# ProcessorSupport.net
KiCad netlist of a schematic drawn in Altium Designer
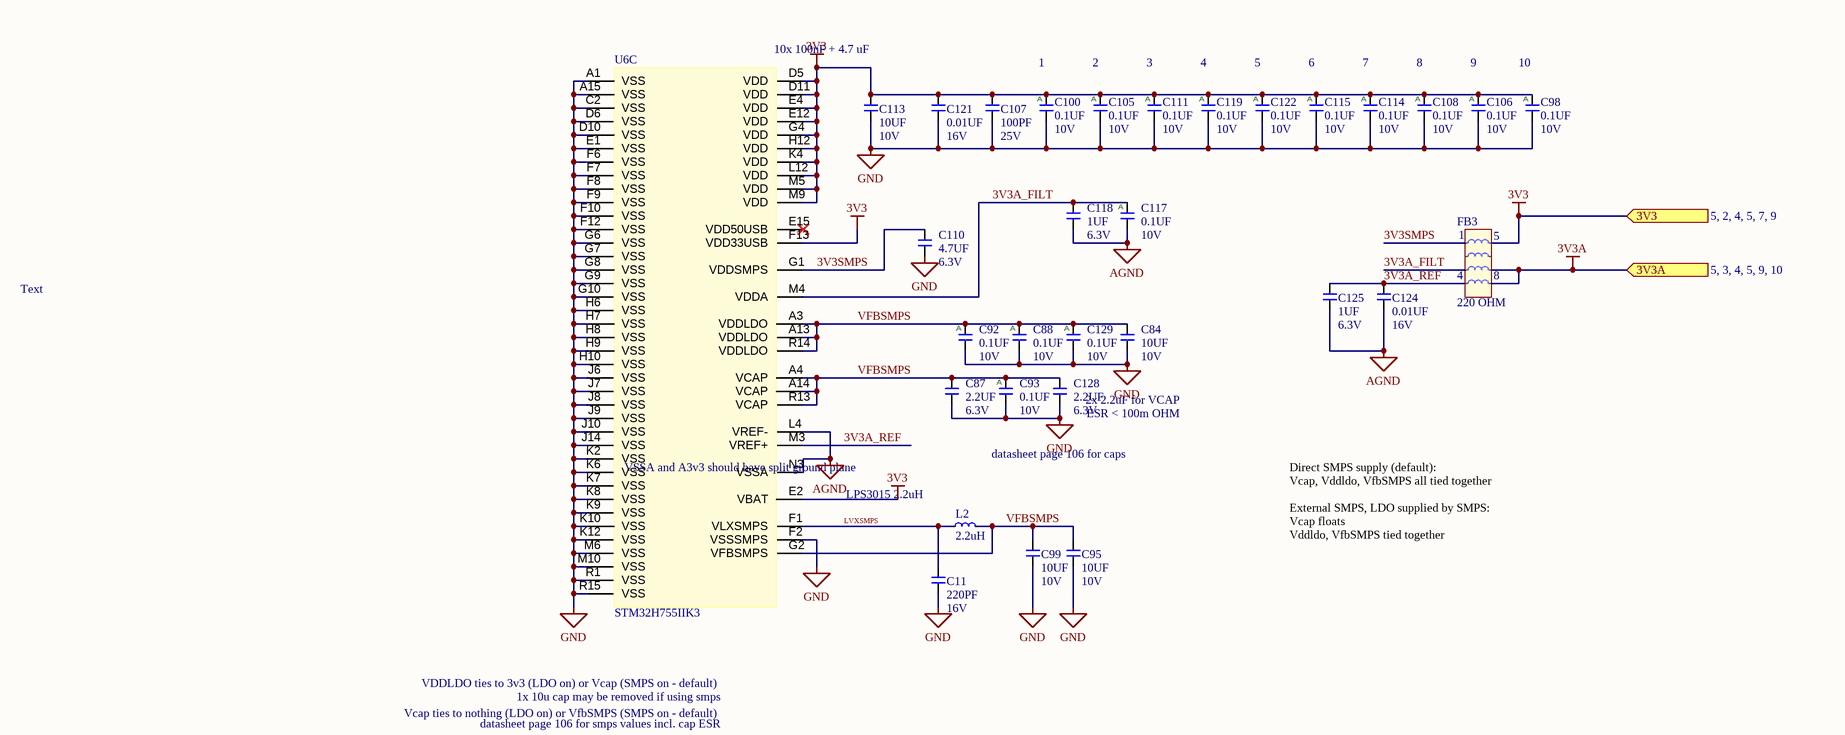
[diagram p0: ProcessorSupport.SchDoc]

(export (version "E")
  (design (tool "Eeschema 10.0.6"))
  (components
    (comp (ref "C11")
      (value "220PF")
      (footprint "C0201")
      (description "CAP, CER, X7R, 220pF, 16V, 10%, 0201, 0.33mm T")
      (fields
        (field (name "MFG") "MURATA")
        (field (name "VOLTAGE") "16V")
        (field (name "Comment") "__Template_Cap")
      )
      (libsource (lib "AltiumReleaseLibDB") (part "__Template_Cap"))
    )
    (comp (ref "C84")
      (value "10UF")
      (footprint "C0402")
      (description "CAP, CER, X5R, 10uF, 10V, 20%, 0402, 0.7mm T")
      (fields
        (field (name "MFG") "SAMSUNG")
        (field (name "VOLTAGE") "10V")
        (field (name "Comment") "__Template_Cap")
      )
      (libsource (lib "AltiumReleaseLibDB") (part "__Template_Cap"))
    )
    (comp (ref "C87")
      (value "2.2UF")
      (footprint "C0201")
      (description "CAP, CER, X5R, 2.2uF, 6.3V, 20%, 0201, 0.39mm T")
      (fields
        (field (name "MFG") "SAMSUNG")
        (field (name "VOLTAGE") "6.3V")
        (field (name "Comment") "__Template_Cap")
      )
      (libsource (lib "AltiumReleaseLibDB") (part "__Template_Cap"))
    )
    (comp (ref "C88")
      (value "0.1UF")
      (footprint "C0201")
      (description "CAP, CER, X6S, 0.1uF, 10V, 10%, 0201, AUTOGRADE")
      (fields
        (field (name "MFG") "MURATA")
        (field (name "VOLTAGE") "10V")
        (field (name "Comment") "__Template_Cap_Auto")
      )
      (libsource (lib "AltiumReleaseLibDB") (part "__Template_Cap_Auto"))
    )
    (comp (ref "C92")
      (value "0.1UF")
      (footprint "C0201")
      (description "CAP, CER, X6S, 0.1uF, 10V, 10%, 0201, AUTOGRADE")
      (fields
        (field (name "MFG") "MURATA")
        (field (name "VOLTAGE") "10V")
        (field (name "Comment") "__Template_Cap_Auto")
      )
      (libsource (lib "AltiumReleaseLibDB") (part "__Template_Cap_Auto"))
    )
    (comp (ref "C93")
      (value "0.1UF")
      (footprint "C0201")
      (description "CAP, CER, X6S, 0.1uF, 10V, 10%, 0201, AUTOGRADE")
      (fields
        (field (name "MFG") "MURATA")
        (field (name "VOLTAGE") "10V")
        (field (name "Comment") "__Template_Cap_Auto")
      )
      (libsource (lib "AltiumReleaseLibDB") (part "__Template_Cap_Auto"))
    )
    (comp (ref "C95")
      (value "10UF")
      (footprint "C0402")
      (description "CAP, CER, X5R, 10uF, 10V, 20%, 0402, 0.7mm T")
      (fields
        (field (name "MFG") "SAMSUNG")
        (field (name "VOLTAGE") "10V")
        (field (name "Comment") "__Template_Cap")
      )
      (libsource (lib "AltiumReleaseLibDB") (part "__Template_Cap"))
    )
    (comp (ref "C98")
      (value "0.1UF")
      (footprint "C0201")
      (description "CAP, CER, X6S, 0.1uF, 10V, 10%, 0201, AUTOGRADE")
      (fields
        (field (name "MFG") "MURATA")
        (field (name "VOLTAGE") "10V")
        (field (name "Comment") "__Template_Cap_Auto")
      )
      (libsource (lib "AltiumReleaseLibDB") (part "__Template_Cap_Auto"))
    )
    (comp (ref "C99")
      (value "10UF")
      (footprint "C0402")
      (description "CAP, CER, X5R, 10uF, 10V, 20%, 0402, 0.7mm T")
      (fields
        (field (name "MFG") "SAMSUNG")
        (field (name "VOLTAGE") "10V")
        (field (name "Comment") "__Template_Cap")
      )
      (libsource (lib "AltiumReleaseLibDB") (part "__Template_Cap"))
    )
    (comp (ref "C100")
      (value "0.1UF")
      (footprint "C0201")
      (description "CAP, CER, X6S, 0.1uF, 10V, 10%, 0201, AUTOGRADE")
      (fields
        (field (name "MFG") "MURATA")
        (field (name "VOLTAGE") "10V")
        (field (name "Comment") "__Template_Cap_Auto")
      )
      (libsource (lib "AltiumReleaseLibDB") (part "__Template_Cap_Auto"))
    )
    (comp (ref "C105")
      (value "0.1UF")
      (footprint "C0201")
      (description "CAP, CER, X6S, 0.1uF, 10V, 10%, 0201, AUTOGRADE")
      (fields
        (field (name "MFG") "MURATA")
        (field (name "VOLTAGE") "10V")
        (field (name "Comment") "__Template_Cap_Auto")
      )
      (libsource (lib "AltiumReleaseLibDB") (part "__Template_Cap_Auto"))
    )
    (comp (ref "C106")
      (value "0.1UF")
      (footprint "C0201")
      (description "CAP, CER, X6S, 0.1uF, 10V, 10%, 0201, AUTOGRADE")
      (fields
        (field (name "MFG") "MURATA")
        (field (name "VOLTAGE") "10V")
        (field (name "Comment") "__Template_Cap_Auto")
      )
      (libsource (lib "AltiumReleaseLibDB") (part "__Template_Cap_Auto"))
    )
    (comp (ref "C107")
      (value "100PF")
      (footprint "C0201")
      (description "CAP, CER, X7R, 100pF, 25V, 10%, 0201, 0.33mm T")
      (fields
        (field (name "MFG") "MURATA")
        (field (name "VOLTAGE") "25V")
        (field (name "Comment") "__Template_Cap")
      )
      (libsource (lib "AltiumReleaseLibDB") (part "__Template_Cap"))
    )
    (comp (ref "C108")
      (value "0.1UF")
      (footprint "C0201")
      (description "CAP, CER, X6S, 0.1uF, 10V, 10%, 0201, AUTOGRADE")
      (fields
        (field (name "MFG") "MURATA")
        (field (name "VOLTAGE") "10V")
        (field (name "Comment") "__Template_Cap_Auto")
      )
      (libsource (lib "AltiumReleaseLibDB") (part "__Template_Cap_Auto"))
    )
    (comp (ref "C110")
      (value "4.7UF")
      (footprint "C0402")
      (description "CAP, CER, X5R, 4.7uF, 20%, 6.3V, 0402, 0.65mm")
      (fields
        (field (name "MFG") "TDK")
        (field (name "VOLTAGE") "6.3V")
        (field (name "Comment") "__Template_Cap")
      )
      (libsource (lib "AltiumReleaseLibDB") (part "__Template_Cap"))
    )
    (comp (ref "C111")
      (value "0.1UF")
      (footprint "C0201")
      (description "CAP, CER, X6S, 0.1uF, 10V, 10%, 0201, AUTOGRADE")
      (fields
        (field (name "MFG") "MURATA")
        (field (name "VOLTAGE") "10V")
        (field (name "Comment") "__Template_Cap_Auto")
      )
      (libsource (lib "AltiumReleaseLibDB") (part "__Template_Cap_Auto"))
    )
    (comp (ref "C113")
      (value "10UF")
      (footprint "C0402")
      (description "CAP, CER, X5R, 10uF, 10V, 20%, 0402, 0.7mm T")
      (fields
        (field (name "MFG") "SAMSUNG")
        (field (name "VOLTAGE") "10V")
        (field (name "Comment") "__Template_Cap")
      )
      (libsource (lib "AltiumReleaseLibDB") (part "__Template_Cap"))
    )
    (comp (ref "C114")
      (value "0.1UF")
      (footprint "C0201")
      (description "CAP, CER, X6S, 0.1uF, 10V, 10%, 0201, AUTOGRADE")
      (fields
        (field (name "MFG") "MURATA")
        (field (name "VOLTAGE") "10V")
        (field (name "Comment") "__Template_Cap_Auto")
      )
      (libsource (lib "AltiumReleaseLibDB") (part "__Template_Cap_Auto"))
    )
    (comp (ref "C115")
      (value "0.1UF")
      (footprint "C0201")
      (description "CAP, CER, X6S, 0.1uF, 10V, 10%, 0201, AUTOGRADE")
      (fields
        (field (name "MFG") "MURATA")
        (field (name "VOLTAGE") "10V")
        (field (name "Comment") "__Template_Cap_Auto")
      )
      (libsource (lib "AltiumReleaseLibDB") (part "__Template_Cap_Auto"))
    )
    (comp (ref "C117")
      (value "0.1UF")
      (footprint "C0201")
      (description "CAP, CER, X6S, 0.1uF, 10V, 10%, 0201, AUTOGRADE")
      (fields
        (field (name "MFG") "MURATA")
        (field (name "VOLTAGE") "10V")
        (field (name "Comment") "__Template_Cap_Auto")
      )
      (libsource (lib "AltiumReleaseLibDB") (part "__Template_Cap_Auto"))
    )
    (comp (ref "C118")
      (value "1UF")
      (footprint "C0201")
      (description "CAP, CER, X5R, 1uF, 6.3V, 20%, 0201, 0.33mm T")
      (fields
        (field (name "MFG") "SAMSUNG")
        (field (name "VOLTAGE") "6.3V")
        (field (name "Comment") "__Template_Cap")
      )
      (libsource (lib "AltiumReleaseLibDB") (part "__Template_Cap"))
    )
    (comp (ref "C119")
      (value "0.1UF")
      (footprint "C0201")
      (description "CAP, CER, X6S, 0.1uF, 10V, 10%, 0201, AUTOGRADE")
      (fields
        (field (name "MFG") "MURATA")
        (field (name "VOLTAGE") "10V")
        (field (name "Comment") "__Template_Cap_Auto")
      )
      (libsource (lib "AltiumReleaseLibDB") (part "__Template_Cap_Auto"))
    )
    (comp (ref "C121")
      (value "0.01UF")
      (footprint "C0201")
      (description "CAP, CER, X5R, 0.01uF, 16V, 10%, 0201, 0.33mm T")
      (fields
        (field (name "MFG") "MURATA")
        (field (name "VOLTAGE") "16V")
        (field (name "Comment") "__Template_Cap")
      )
      (libsource (lib "AltiumReleaseLibDB") (part "__Template_Cap"))
    )
    (comp (ref "C122")
      (value "0.1UF")
      (footprint "C0201")
      (description "CAP, CER, X6S, 0.1uF, 10V, 10%, 0201, AUTOGRADE")
      (fields
        (field (name "MFG") "MURATA")
        (field (name "VOLTAGE") "10V")
        (field (name "Comment") "__Template_Cap_Auto")
      )
      (libsource (lib "AltiumReleaseLibDB") (part "__Template_Cap_Auto"))
    )
    (comp (ref "C124")
      (value "0.01UF")
      (footprint "C0201")
      (description "CAP, CER, X5R, 0.01uF, 16V, 10%, 0201, 0.33mm T")
      (fields
        (field (name "MFG") "MURATA")
        (field (name "VOLTAGE") "16V")
        (field (name "Comment") "__Template_Cap")
      )
      (libsource (lib "AltiumReleaseLibDB") (part "__Template_Cap"))
    )
    (comp (ref "C125")
      (value "1UF")
      (footprint "C0201")
      (description "CAP, CER, X5R, 1uF, 6.3V, 20%, 0201, 0.33mm T")
      (fields
        (field (name "MFG") "SAMSUNG")
        (field (name "VOLTAGE") "6.3V")
        (field (name "Comment") "__Template_Cap")
      )
      (libsource (lib "AltiumReleaseLibDB") (part "__Template_Cap"))
    )
    (comp (ref "C128")
      (value "2.2UF")
      (footprint "C0201")
      (description "CAP, CER, X5R, 2.2uF, 6.3V, 20%, 0201, 0.39mm T")
      (fields
        (field (name "MFG") "SAMSUNG")
        (field (name "VOLTAGE") "6.3V")
        (field (name "Comment") "__Template_Cap")
      )
      (libsource (lib "AltiumReleaseLibDB") (part "__Template_Cap"))
    )
    (comp (ref "C129")
      (value "0.1UF")
      (footprint "C0201")
      (description "CAP, CER, X6S, 0.1uF, 10V, 10%, 0201, AUTOGRADE")
      (fields
        (field (name "MFG") "MURATA")
        (field (name "VOLTAGE") "10V")
        (field (name "Comment") "__Template_Cap_Auto")
      )
      (libsource (lib "AltiumReleaseLibDB") (part "__Template_Cap_Auto"))
    )
    (comp (ref "FB3")
      (value "220 OHM")
      (footprint "FB_ARRAY_BLA31AG221SN4D")
      (description "FERRITE, BEAD, 220 OHM, 150mA, DCR 0.25 MAX, 1206")
      (fields (field (name "MFG") "Murata Electronics") (field (name "Comment") "FB_ARRAY_BLA31AG221SN4D"))
      (libsource (lib "AltiumReleaseLibDB") (part "FB_ARRAY_BLA31AG221SN4D"))
    )
    (comp (ref "L2")
      (value "2.2uH")
      (footprint "IND_LPS3015-152MRB")
      (description "IND, WIREWOUND, SHIELDED, 2.2uH, 2.1A, 20%, DCR 0.11, SMD, AUTOGRADE")
      (fields (field (name "MFG") "COILCRAFT") (field (name "Comment") "__Template_Inductor"))
      (libsource (lib "AltiumReleaseLibDB") (part "__Template_Inductor"))
    )
    (comp (ref "U6")
      (value "MCU_STM32H755IIK3")
      (footprint "BGS201C65P15X15_1000X1000X60")
      (description "IC, MCU, STM32H755xI, ARM, 32-BIT, 240MHZ, 128 I/O, 2MB, FLASH, 1.62V TO 3.6V, UFBGA-201")
      (fields (field (name "MFG") "STMicroelectronics") (field (name "MFG P/N") "STM32H755IIK3"))
      (libsource (lib "AltiumReleaseLibDB") (part "MCU_STM32H755IIK3"))
    )
  )
  (nets
    (net (code "1") (name "/3V3A_FILT") (class "Default")
      (node (ref "C117") (pin "1") (pintype "passive"))
      (node (ref "C118") (pin "1") (pintype "passive"))
      (node (ref "FB3") (pin "3") (pinfunction "3_3") (pintype "passive"))
      (node (ref "U6") (pin "M4") (pinfunction "VDDA_M4") (pintype "power_in"))
    )
    (net (code "2") (name "/3V3A_REF") (class "Default")
      (node (ref "C124") (pin "1") (pintype "passive"))
      (node (ref "C125") (pin "1") (pintype "passive"))
      (node (ref "FB3") (pin "4") (pinfunction "4_4") (pintype "passive"))
      (node (ref "U6") (pin "M3") (pinfunction "VREF+_M3") (pintype "power_in"))
    )
    (net (code "3") (name "/3V3SMPS") (class "Default")
      (node (ref "C110") (pin "1") (pintype "passive"))
      (node (ref "FB3") (pin "1") (pinfunction "1_1") (pintype "passive"))
      (node (ref "U6") (pin "G1") (pinfunction "VDDSMPS_G1") (pintype "power_in"))
    )
    (net (code "4") (name "/LVXSMPS") (class "Default")
      (node (ref "C11") (pin "1") (pintype "passive"))
      (node (ref "L2") (pin "1") (pintype "passive"))
      (node (ref "U6") (pin "F1") (pinfunction "VLXSMPS_F1") (pintype "power_in"))
    )
    (net (code "5") (name "/VFBSMPS") (class "Default")
      (node (ref "C128") (pin "1") (pintype "passive"))
      (node (ref "C129") (pin "1") (pintype "passive"))
      (node (ref "C84") (pin "1") (pintype "passive"))
      (node (ref "C87") (pin "1") (pintype "passive"))
      (node (ref "C88") (pin "1") (pintype "passive"))
      (node (ref "C92") (pin "1") (pintype "passive"))
      (node (ref "C93") (pin "1") (pintype "passive"))
      (node (ref "C95") (pin "2") (pintype "passive"))
      (node (ref "C99") (pin "2") (pintype "passive"))
      (node (ref "L2") (pin "2") (pintype "passive"))
      (node (ref "U6") (pin "A13") (pinfunction "VDDLDO_A13") (pintype "power_in"))
      (node (ref "U6") (pin "A14") (pinfunction "VCAP_A14") (pintype "power_in"))
      (node (ref "U6") (pin "A3") (pinfunction "VDDLDO_A3") (pintype "power_in"))
      (node (ref "U6") (pin "A4") (pinfunction "VCAP_A4") (pintype "power_in"))
      (node (ref "U6") (pin "G2") (pinfunction "VFBSMPS_G2") (pintype "power_in"))
      (node (ref "U6") (pin "R13") (pinfunction "VCAP_R13") (pintype "power_in"))
      (node (ref "U6") (pin "R14") (pinfunction "VDDLDO_R14") (pintype "power_in"))
    )
    (net (code "6") (name "3V3") (class "Default")
      (node (ref "C100") (pin "1") (pintype "passive"))
      (node (ref "C105") (pin "1") (pintype "passive"))
      (node (ref "C106") (pin "1") (pintype "passive"))
      (node (ref "C107") (pin "1") (pintype "passive"))
      (node (ref "C108") (pin "1") (pintype "passive"))
      (node (ref "C111") (pin "1") (pintype "passive"))
      (node (ref "C113") (pin "1") (pintype "passive"))
      (node (ref "C114") (pin "1") (pintype "passive"))
      (node (ref "C115") (pin "1") (pintype "passive"))
      (node (ref "C119") (pin "1") (pintype "passive"))
      (node (ref "C121") (pin "1") (pintype "passive"))
      (node (ref "C122") (pin "1") (pintype "passive"))
      (node (ref "C98") (pin "1") (pintype "passive"))
      (node (ref "FB3") (pin "5") (pinfunction "5_5") (pintype "passive"))
      (node (ref "U6") (pin "D11") (pinfunction "VDD_D11") (pintype "power_in"))
      (node (ref "U6") (pin "D5") (pinfunction "VDD_D5") (pintype "power_in"))
      (node (ref "U6") (pin "E12") (pinfunction "VDD_E12") (pintype "power_in"))
      (node (ref "U6") (pin "E2") (pinfunction "VBAT_E2") (pintype "power_in"))
      (node (ref "U6") (pin "E4") (pinfunction "VDD_E4") (pintype "power_in"))
      (node (ref "U6") (pin "F13") (pinfunction "VDD33USB_F13") (pintype "power_in"))
      (node (ref "U6") (pin "G4") (pinfunction "VDD_G4") (pintype "power_in"))
      (node (ref "U6") (pin "H12") (pinfunction "VDD_H12") (pintype "power_in"))
      (node (ref "U6") (pin "K4") (pinfunction "VDD_K4") (pintype "power_in"))
      (node (ref "U6") (pin "L12") (pinfunction "VDD_L12") (pintype "power_in"))
      (node (ref "U6") (pin "M5") (pinfunction "VDD_M5") (pintype "power_in"))
      (node (ref "U6") (pin "M9") (pinfunction "VDD_M9") (pintype "power_in"))
    )
    (net (code "7") (name "3V3A") (class "Default")
      (node (ref "FB3") (pin "7") (pinfunction "7_7") (pintype "passive"))
      (node (ref "FB3") (pin "8") (pinfunction "8_8") (pintype "passive"))
    )
    (net (code "8") (name "AGND") (class "Default")
      (node (ref "C117") (pin "2") (pintype "passive"))
      (node (ref "C118") (pin "2") (pintype "passive"))
      (node (ref "C124") (pin "2") (pintype "passive"))
      (node (ref "C125") (pin "2") (pintype "passive"))
      (node (ref "U6") (pin "L4") (pinfunction "VREF-_L4") (pintype "power_in"))
      (node (ref "U6") (pin "N3") (pinfunction "VSSA_N3") (pintype "power_in"))
    )
    (net (code "9") (name "GND") (class "Default")
      (node (ref "C100") (pin "2") (pintype "passive"))
      (node (ref "C105") (pin "2") (pintype "passive"))
      (node (ref "C106") (pin "2") (pintype "passive"))
      (node (ref "C107") (pin "2") (pintype "passive"))
      (node (ref "C108") (pin "2") (pintype "passive"))
      (node (ref "C11") (pin "2") (pintype "passive"))
      (node (ref "C110") (pin "2") (pintype "passive"))
      (node (ref "C111") (pin "2") (pintype "passive"))
      (node (ref "C113") (pin "2") (pintype "passive"))
      (node (ref "C114") (pin "2") (pintype "passive"))
      (node (ref "C115") (pin "2") (pintype "passive"))
      (node (ref "C119") (pin "2") (pintype "passive"))
      (node (ref "C121") (pin "2") (pintype "passive"))
      (node (ref "C122") (pin "2") (pintype "passive"))
      (node (ref "C128") (pin "2") (pintype "passive"))
      (node (ref "C129") (pin "2") (pintype "passive"))
      (node (ref "C84") (pin "2") (pintype "passive"))
      (node (ref "C87") (pin "2") (pintype "passive"))
      (node (ref "C88") (pin "2") (pintype "passive"))
      (node (ref "C92") (pin "2") (pintype "passive"))
      (node (ref "C93") (pin "2") (pintype "passive"))
      (node (ref "C95") (pin "1") (pintype "passive"))
      (node (ref "C98") (pin "2") (pintype "passive"))
      (node (ref "C99") (pin "1") (pintype "passive"))
      (node (ref "U6") (pin "A1") (pinfunction "VSS_A1") (pintype "power_in"))
      (node (ref "U6") (pin "A15") (pinfunction "VSS_A15") (pintype "power_in"))
      (node (ref "U6") (pin "C2") (pinfunction "VSS_C2") (pintype "power_in"))
      (node (ref "U6") (pin "D10") (pinfunction "VSS_D10") (pintype "power_in"))
      (node (ref "U6") (pin "D6") (pinfunction "VSS_D6") (pintype "power_in"))
      (node (ref "U6") (pin "E1") (pinfunction "VSS_E1") (pintype "power_in"))
      (node (ref "U6") (pin "F10") (pinfunction "VSS_F10") (pintype "power_in"))
      (node (ref "U6") (pin "F12") (pinfunction "VSS_F12") (pintype "power_in"))
      (node (ref "U6") (pin "F2") (pinfunction "VSSSMPS_F2") (pintype "power_in"))
      (node (ref "U6") (pin "F6") (pinfunction "VSS_F6") (pintype "power_in"))
      (node (ref "U6") (pin "F7") (pinfunction "VSS_F7") (pintype "power_in"))
      (node (ref "U6") (pin "F8") (pinfunction "VSS_F8") (pintype "power_in"))
      (node (ref "U6") (pin "F9") (pinfunction "VSS_F9") (pintype "power_in"))
      (node (ref "U6") (pin "G10") (pinfunction "VSS_G10") (pintype "power_in"))
      (node (ref "U6") (pin "G6") (pinfunction "VSS_G6") (pintype "power_in"))
      (node (ref "U6") (pin "G7") (pinfunction "VSS_G7") (pintype "power_in"))
      (node (ref "U6") (pin "G8") (pinfunction "VSS_G8") (pintype "power_in"))
      (node (ref "U6") (pin "G9") (pinfunction "VSS_G9") (pintype "power_in"))
      (node (ref "U6") (pin "H10") (pinfunction "VSS_H10") (pintype "power_in"))
      (node (ref "U6") (pin "H6") (pinfunction "VSS_H6") (pintype "power_in"))
      (node (ref "U6") (pin "H7") (pinfunction "VSS_H7") (pintype "power_in"))
      (node (ref "U6") (pin "H8") (pinfunction "VSS_H8") (pintype "power_in"))
      (node (ref "U6") (pin "H9") (pinfunction "VSS_H9") (pintype "power_in"))
      (node (ref "U6") (pin "J10") (pinfunction "VSS_J10") (pintype "power_in"))
      (node (ref "U6") (pin "J14") (pinfunction "VSS_J14") (pintype "power_in"))
      (node (ref "U6") (pin "J6") (pinfunction "VSS_J6") (pintype "power_in"))
      (node (ref "U6") (pin "J7") (pinfunction "VSS_J7") (pintype "power_in"))
      (node (ref "U6") (pin "J8") (pinfunction "VSS_J8") (pintype "power_in"))
      (node (ref "U6") (pin "J9") (pinfunction "VSS_J9") (pintype "power_in"))
      (node (ref "U6") (pin "K10") (pinfunction "VSS_K10") (pintype "power_in"))
      (node (ref "U6") (pin "K12") (pinfunction "VSS_K12") (pintype "power_in"))
      (node (ref "U6") (pin "K2") (pinfunction "VSS_K2") (pintype "power_in"))
      (node (ref "U6") (pin "K6") (pinfunction "VSS_K6") (pintype "power_in"))
      (node (ref "U6") (pin "K7") (pinfunction "VSS_K7") (pintype "power_in"))
      (node (ref "U6") (pin "K8") (pinfunction "VSS_K8") (pintype "power_in"))
      (node (ref "U6") (pin "K9") (pinfunction "VSS_K9") (pintype "power_in"))
      (node (ref "U6") (pin "M10") (pinfunction "VSS_M10") (pintype "power_in"))
      (node (ref "U6") (pin "M6") (pinfunction "VSS_M6") (pintype "power_in"))
      (node (ref "U6") (pin "R1") (pinfunction "VSS_R1") (pintype "power_in"))
      (node (ref "U6") (pin "R15") (pinfunction "VSS_R15") (pintype "power_in"))
    )
    (net (code "10") (name "unconnected-(FB3-Pad2)") (class "Default")
      (node (ref "FB3") (pin "2") (pinfunction "2_2") (pintype "passive"))
    )
    (net (code "11") (name "unconnected-(FB3-Pad6)") (class "Default")
      (node (ref "FB3") (pin "6") (pinfunction "6_6") (pintype "passive"))
    )
    (net (code "12") (name "unconnected-(U6C-VDD50USB-PadE15)") (class "Default")
      (node (ref "U6") (pin "E15") (pinfunction "VDD50USB_E15") (pintype "power_in+no_connect"))
    )
  )
)
